# Output.net
KiCad netlist of a schematic drawn in Altium Designer
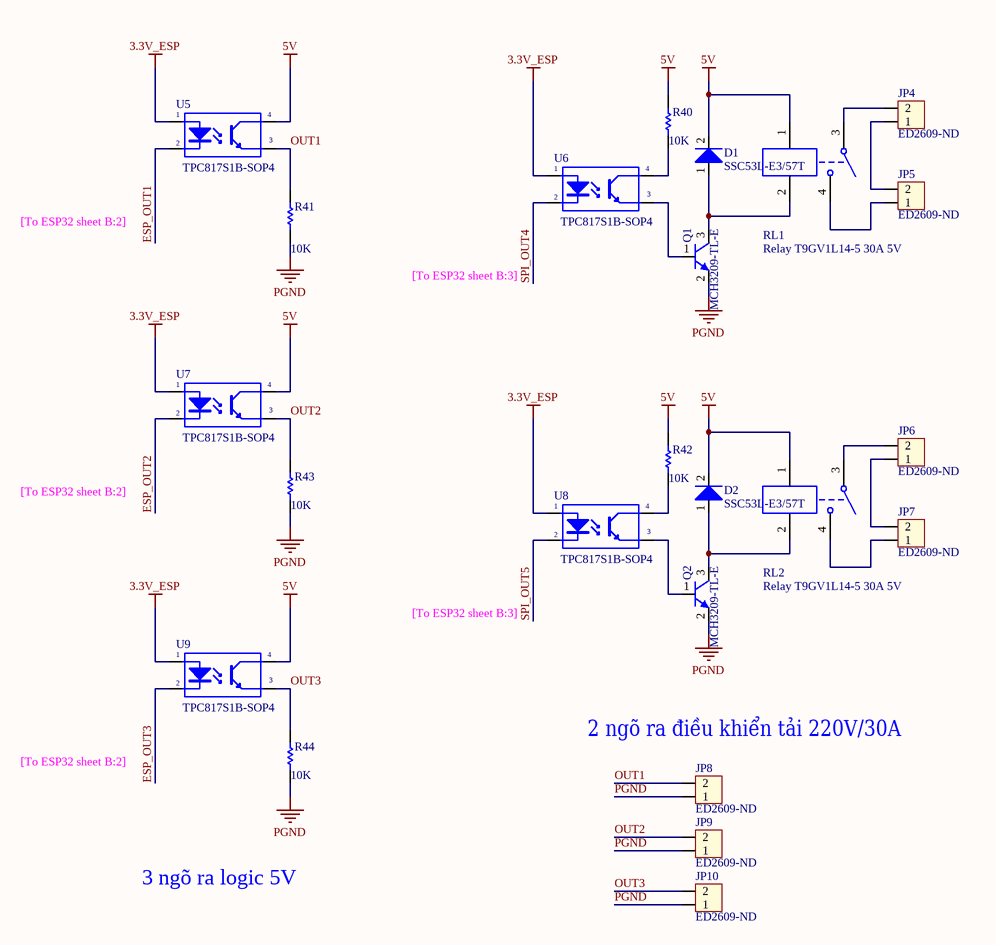
[diagram p0: Output.SchDoc]

(export (version "E")
  (design (tool "Eeschema 10.0.6"))
  (components
    (comp (ref "D1")
      (value "SSC53L-E3/57T")
      (footprint "SSC53L-E3/57T")
      (description "DIODE SCHOTTKY 30V 5A DO214AB")
      (libsource (lib "lpson") (part "10A10"))
    )
    (comp (ref "D2")
      (value "SSC53L-E3/57T")
      (footprint "SSC53L-E3/57T")
      (description "DIODE SCHOTTKY 30V 5A DO214AB")
      (libsource (lib "lpson") (part "10A10"))
    )
    (comp (ref "JP4")
      (value "ED2609-ND")
      (footprint "DOMINO_OSTTC_2P")
      (description "2 Position Wire to Board Terminal Block Horizontal with Board 0.200\" (5.08mm) Through Hole")
      (libsource (lib "lpson") (part "Con2"))
    )
    (comp (ref "JP5")
      (value "ED2609-ND")
      (footprint "DOMINO_OSTTC_2P")
      (description "2 Position Wire to Board Terminal Block Horizontal with Board 0.200\" (5.08mm) Through Hole")
      (libsource (lib "lpson") (part "Con2"))
    )
    (comp (ref "JP6")
      (value "ED2609-ND")
      (footprint "DOMINO_OSTTC_2P")
      (description "2 Position Wire to Board Terminal Block Horizontal with Board 0.200\" (5.08mm) Through Hole")
      (libsource (lib "lpson") (part "Con2"))
    )
    (comp (ref "JP7")
      (value "ED2609-ND")
      (footprint "DOMINO_OSTTC_2P")
      (description "2 Position Wire to Board Terminal Block Horizontal with Board 0.200\" (5.08mm) Through Hole")
      (libsource (lib "lpson") (part "Con2"))
    )
    (comp (ref "JP8")
      (value "ED2609-ND")
      (footprint "DOMINO_OSTTC_2P")
      (description "2 Position Wire to Board Terminal Block Horizontal with Board 0.200\" (5.08mm) Through Hole")
      (libsource (lib "lpson") (part "Con2"))
    )
    (comp (ref "JP9")
      (value "ED2609-ND")
      (footprint "DOMINO_OSTTC_2P")
      (description "2 Position Wire to Board Terminal Block Horizontal with Board 0.200\" (5.08mm) Through Hole")
      (libsource (lib "lpson") (part "Con2"))
    )
    (comp (ref "JP10")
      (value "ED2609-ND")
      (footprint "DOMINO_OSTTC_2P")
      (description "2 Position Wire to Board Terminal Block Horizontal with Board 0.200\" (5.08mm) Through Hole")
      (libsource (lib "lpson") (part "Con2"))
    )
    (comp (ref "Q1")
      (value "MCH3209-TL-E")
      (footprint "MCH3209-TL-E  SOT-323")
      (description "Bipolar (BJT) Transistor NPN 30V 3A 450MHz 800mW Surface Mount 3-MCPH")
      (libsource (lib "lpson") (part "2SC1815"))
    )
    (comp (ref "Q2")
      (value "MCH3209-TL-E")
      (footprint "MCH3209-TL-E  SOT-323")
      (description "Bipolar (BJT) Transistor NPN 30V 3A 450MHz 800mW Surface Mount 3-MCPH")
      (libsource (lib "lpson") (part "2SC1815"))
    )
    (comp (ref "R40")
      (value "10K")
      (footprint "Res 0805 SMD")
      (description "RES SMD 249K OHM 1% 1/10W 0805")
      (fields
        (field (name "MANUFACTURER") "Yageo")
        (field (name "MANUFACTURER PART NUMBER") "RC0603FR-07249KL")
      )
      (libsource (lib "GSHT_181013") (part "249K/R0805/1%"))
    )
    (comp (ref "R41")
      (value "10K")
      (footprint "Res 0805 SMD")
      (description "RES SMD 249K OHM 1% 1/10W 0805")
      (fields
        (field (name "MANUFACTURER") "Yageo")
        (field (name "MANUFACTURER PART NUMBER") "RC0603FR-07249KL")
      )
      (libsource (lib "GSHT_181013") (part "249K/R0805/1%"))
    )
    (comp (ref "R42")
      (value "10K")
      (footprint "Res 0805 SMD")
      (description "RES SMD 249K OHM 1% 1/10W 0805")
      (fields
        (field (name "MANUFACTURER") "Yageo")
        (field (name "MANUFACTURER PART NUMBER") "RC0603FR-07249KL")
      )
      (libsource (lib "GSHT_181013") (part "249K/R0805/1%"))
    )
    (comp (ref "R43")
      (value "10K")
      (footprint "Res 0805 SMD")
      (description "RES SMD 249K OHM 1% 1/10W 0805")
      (fields
        (field (name "MANUFACTURER") "Yageo")
        (field (name "MANUFACTURER PART NUMBER") "RC0603FR-07249KL")
      )
      (libsource (lib "GSHT_181013") (part "249K/R0805/1%"))
    )
    (comp (ref "R44")
      (value "10K")
      (footprint "Res 0805 SMD")
      (description "RES SMD 249K OHM 1% 1/10W 0805")
      (fields
        (field (name "MANUFACTURER") "Yageo")
        (field (name "MANUFACTURER PART NUMBER") "RC0603FR-07249KL")
      )
      (libsource (lib "GSHT_181013") (part "249K/R0805/1%"))
    )
    (comp (ref "RL1")
      (value "Relay T9GV1L14-5 30A 5V")
      (footprint "Relay T9GV1L14-5 30A 5V")
      (description "General Purpose Relay SPST-NO (1 Form A) 5VDC Coil Through Hole")
      (libsource (lib "PCB_ESP32_RFID") (part "Relay T9GV1L14-5 30A 5V"))
    )
    (comp (ref "RL2")
      (value "Relay T9GV1L14-5 30A 5V")
      (footprint "Relay T9GV1L14-5 30A 5V")
      (description "General Purpose Relay SPST-NO (1 Form A) 5VDC Coil Through Hole")
      (libsource (lib "PCB_ESP32_RFID") (part "Relay T9GV1L14-5 30A 5V"))
    )
    (comp (ref "U5")
      (value "TPC817S1B-SOP4")
      (footprint "TPC817-4SOP")
      (description "Optoisolator Transistor Output 5000Vrms 1 Channel 4-SOP")
      (libsource (lib "lpson") (part "PC817"))
    )
    (comp (ref "U6")
      (value "TPC817S1B-SOP4")
      (footprint "TPC817-4SOP")
      (description "Optoisolator Transistor Output 5000Vrms 1 Channel 4-SOP")
      (libsource (lib "lpson") (part "PC817"))
    )
    (comp (ref "U7")
      (value "TPC817S1B-SOP4")
      (footprint "TPC817-4SOP")
      (description "Optoisolator Transistor Output 5000Vrms 1 Channel 4-SOP")
      (libsource (lib "lpson") (part "PC817"))
    )
    (comp (ref "U8")
      (value "TPC817S1B-SOP4")
      (footprint "TPC817-4SOP")
      (description "Optoisolator Transistor Output 5000Vrms 1 Channel 4-SOP")
      (libsource (lib "lpson") (part "PC817"))
    )
    (comp (ref "U9")
      (value "TPC817S1B-SOP4")
      (footprint "TPC817-4SOP")
      (description "Optoisolator Transistor Output 5000Vrms 1 Channel 4-SOP")
      (libsource (lib "lpson") (part "PC817"))
    )
  )
  (nets
    (net (code "1") (name "/ESP_OUT1") (class "Default")
      (node (ref "U5") (pin "2") (pinfunction "K_2") (pintype "passive"))
    )
    (net (code "2") (name "/ESP_OUT2") (class "Default")
      (node (ref "U7") (pin "2") (pinfunction "K_2") (pintype "passive"))
    )
    (net (code "3") (name "/ESP_OUT3") (class "Default")
      (node (ref "U9") (pin "2") (pinfunction "K_2") (pintype "passive"))
    )
    (net (code "4") (name "/OUT1") (class "Default")
      (node (ref "JP8") (pin "2") (pinfunction "2_2") (pintype "passive"))
      (node (ref "R41") (pin "2") (pinfunction "2_2") (pintype "passive"))
      (node (ref "U5") (pin "3") (pinfunction "E_3") (pintype "passive"))
    )
    (net (code "5") (name "/OUT2") (class "Default")
      (node (ref "JP9") (pin "2") (pinfunction "2_2") (pintype "passive"))
      (node (ref "R43") (pin "2") (pinfunction "2_2") (pintype "passive"))
      (node (ref "U7") (pin "3") (pinfunction "E_3") (pintype "passive"))
    )
    (net (code "6") (name "/OUT3") (class "Default")
      (node (ref "JP10") (pin "2") (pinfunction "2_2") (pintype "passive"))
      (node (ref "R44") (pin "2") (pinfunction "2_2") (pintype "passive"))
      (node (ref "U9") (pin "3") (pinfunction "E_3") (pintype "passive"))
    )
    (net (code "7") (name "/SPI_OUT4") (class "Default")
      (node (ref "U6") (pin "2") (pinfunction "K_2") (pintype "passive"))
    )
    (net (code "8") (name "/SPI_OUT5") (class "Default")
      (node (ref "U8") (pin "2") (pinfunction "K_2") (pintype "passive"))
    )
    (net (code "9") (name "3.3V_ESP") (class "Default")
      (node (ref "U5") (pin "1") (pinfunction "A_1") (pintype "passive"))
      (node (ref "U6") (pin "1") (pinfunction "A_1") (pintype "passive"))
      (node (ref "U7") (pin "1") (pinfunction "A_1") (pintype "passive"))
      (node (ref "U8") (pin "1") (pinfunction "A_1") (pintype "passive"))
      (node (ref "U9") (pin "1") (pinfunction "A_1") (pintype "passive"))
    )
    (net (code "10") (name "5V") (class "Default")
      (node (ref "D1") (pin "2") (pinfunction "K_2") (pintype "passive"))
      (node (ref "D2") (pin "2") (pinfunction "K_2") (pintype "passive"))
      (node (ref "R40") (pin "2") (pinfunction "2_2") (pintype "passive"))
      (node (ref "R42") (pin "2") (pinfunction "2_2") (pintype "passive"))
      (node (ref "RL1") (pin "1") (pinfunction "1_1") (pintype "passive"))
      (node (ref "RL2") (pin "1") (pinfunction "1_1") (pintype "passive"))
      (node (ref "U5") (pin "4") (pinfunction "C_4") (pintype "passive"))
      (node (ref "U7") (pin "4") (pinfunction "C_4") (pintype "passive"))
      (node (ref "U9") (pin "4") (pinfunction "C_4") (pintype "passive"))
    )
    (net (code "11") (name "Net-(D1-A)") (class "Default")
      (node (ref "D1") (pin "1") (pinfunction "A_1") (pintype "passive"))
      (node (ref "Q1") (pin "3") (pinfunction "C_3") (pintype "passive"))
      (node (ref "RL1") (pin "2") (pinfunction "2_2") (pintype "passive"))
    )
    (net (code "12") (name "Net-(D2-A)") (class "Default")
      (node (ref "D2") (pin "1") (pinfunction "A_1") (pintype "passive"))
      (node (ref "Q2") (pin "3") (pinfunction "C_3") (pintype "passive"))
      (node (ref "RL2") (pin "2") (pinfunction "2_2") (pintype "passive"))
    )
    (net (code "13") (name "Net-(JP4-Pad1)") (class "Default")
      (node (ref "JP4") (pin "1") (pinfunction "1_1") (pintype "passive"))
      (node (ref "JP5") (pin "2") (pinfunction "2_2") (pintype "passive"))
    )
    (net (code "14") (name "Net-(JP4-Pad2)") (class "Default")
      (node (ref "JP4") (pin "2") (pinfunction "2_2") (pintype "passive"))
      (node (ref "RL1") (pin "3") (pinfunction "3_3") (pintype "passive"))
    )
    (net (code "15") (name "Net-(JP5-Pad1)") (class "Default")
      (node (ref "JP5") (pin "1") (pinfunction "1_1") (pintype "passive"))
      (node (ref "RL1") (pin "4") (pinfunction "4_4") (pintype "passive"))
    )
    (net (code "16") (name "Net-(JP6-Pad1)") (class "Default")
      (node (ref "JP6") (pin "1") (pinfunction "1_1") (pintype "passive"))
      (node (ref "JP7") (pin "2") (pinfunction "2_2") (pintype "passive"))
    )
    (net (code "17") (name "Net-(JP6-Pad2)") (class "Default")
      (node (ref "JP6") (pin "2") (pinfunction "2_2") (pintype "passive"))
      (node (ref "RL2") (pin "3") (pinfunction "3_3") (pintype "passive"))
    )
    (net (code "18") (name "Net-(JP7-Pad1)") (class "Default")
      (node (ref "JP7") (pin "1") (pinfunction "1_1") (pintype "passive"))
      (node (ref "RL2") (pin "4") (pinfunction "4_4") (pintype "passive"))
    )
    (net (code "19") (name "Net-(Q1-B)") (class "Default")
      (node (ref "Q1") (pin "1") (pinfunction "B_1") (pintype "passive"))
      (node (ref "U6") (pin "3") (pinfunction "E_3") (pintype "passive"))
    )
    (net (code "20") (name "Net-(Q2-B)") (class "Default")
      (node (ref "Q2") (pin "1") (pinfunction "B_1") (pintype "passive"))
      (node (ref "U8") (pin "3") (pinfunction "E_3") (pintype "passive"))
    )
    (net (code "21") (name "Net-(U6-C)") (class "Default")
      (node (ref "R40") (pin "1") (pinfunction "1_1") (pintype "passive"))
      (node (ref "U6") (pin "4") (pinfunction "C_4") (pintype "passive"))
    )
    (net (code "22") (name "Net-(U8-C)") (class "Default")
      (node (ref "R42") (pin "1") (pinfunction "1_1") (pintype "passive"))
      (node (ref "U8") (pin "4") (pinfunction "C_4") (pintype "passive"))
    )
    (net (code "23") (name "PGND") (class "Default")
      (node (ref "JP10") (pin "1") (pinfunction "1_1") (pintype "passive"))
      (node (ref "JP8") (pin "1") (pinfunction "1_1") (pintype "passive"))
      (node (ref "JP9") (pin "1") (pinfunction "1_1") (pintype "passive"))
      (node (ref "Q1") (pin "2") (pinfunction "E_2") (pintype "passive"))
      (node (ref "Q2") (pin "2") (pinfunction "E_2") (pintype "passive"))
      (node (ref "R41") (pin "1") (pinfunction "1_1") (pintype "passive"))
      (node (ref "R43") (pin "1") (pinfunction "1_1") (pintype "passive"))
      (node (ref "R44") (pin "1") (pinfunction "1_1") (pintype "passive"))
    )
  )
)
